# LEDSEQUENCER.net
KiCad netlist of a schematic drawn in Altium Designer
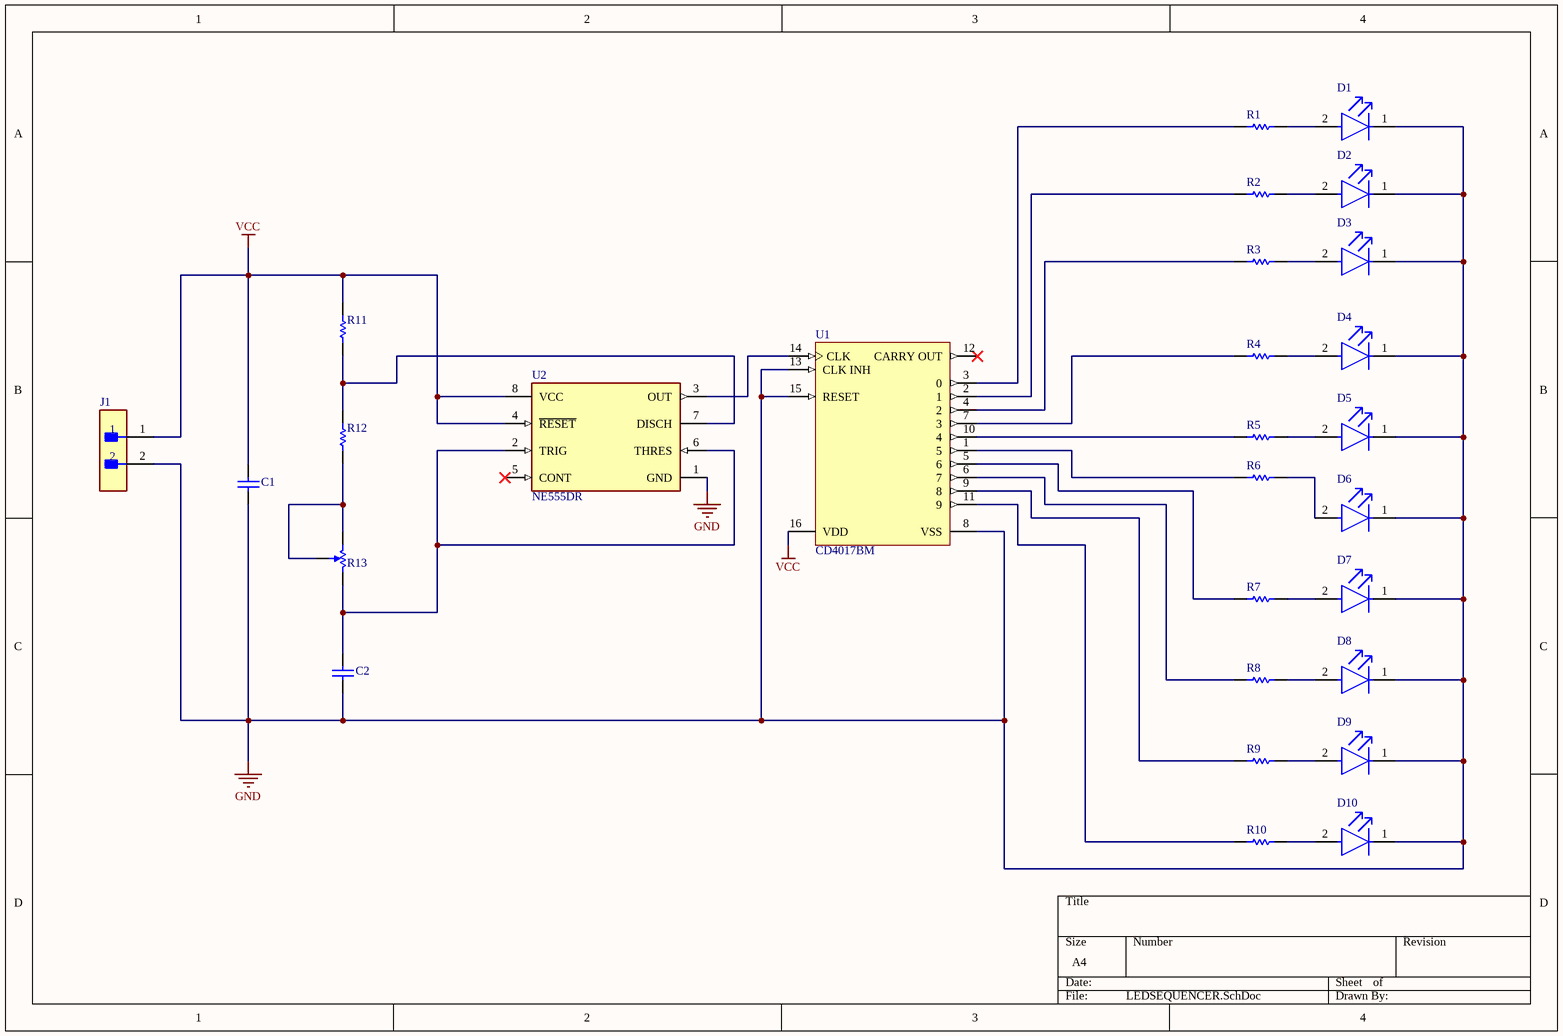
[diagram p0: LEDSEQUENCER.SchDoc]

(export (version "E")
  (design (tool "Eeschema 10.0.6"))
  (components
    (comp (ref "C1")
      (value "1uf")
      (footprint "CAPC2013X135X45LL10T25")
      (fields (field (name "MANUFACTURER") "Murata") (field (name "PART NUMBER") "GRM21BR71H105KA12L"))
      (libsource (lib "Altium Content Vault") (part "CAP"))
    )
    (comp (ref "C2")
      (value "1uf")
      (footprint "CAPC2013X135X45LL10T25")
      (fields (field (name "MANUFACTURER") "Murata") (field (name "PART NUMBER") "GRM21BR71H105KA12L"))
      (libsource (lib "Altium Content Vault") (part "CAP"))
    )
    (comp (ref "D1")
      (value "HLMP-1301")
      (footprint "FP-HLMP-1301-MFG")
      (description "LED RED DIFFUSED T-1 T/H")
      (fields
        (field (name "OCTOPART") "https://octopart.com/hlmp-1301-broadcom-71130345")
        (field (name "MANUFACTURER") "Broadcom")
      )
      (libsource (lib "Altium Content Vault") (part "8706943c75ba83719d021d2fdc84c58"))
    )
    (comp (ref "D2")
      (value "HLMP-1301")
      (footprint "FP-HLMP-1301-MFG")
      (description "LED RED DIFFUSED T-1 T/H")
      (fields
        (field (name "OCTOPART") "https://octopart.com/hlmp-1301-broadcom-71130345")
        (field (name "MANUFACTURER") "Broadcom")
      )
      (libsource (lib "Altium Content Vault") (part "8706943c75ba83719d021d2fdc84c58"))
    )
    (comp (ref "D3")
      (value "HLMP-1301")
      (footprint "FP-HLMP-1301-MFG")
      (description "LED RED DIFFUSED T-1 T/H")
      (fields
        (field (name "OCTOPART") "https://octopart.com/hlmp-1301-broadcom-71130345")
        (field (name "MANUFACTURER") "Broadcom")
      )
      (libsource (lib "Altium Content Vault") (part "8706943c75ba83719d021d2fdc84c58"))
    )
    (comp (ref "D4")
      (value "HLMP-1301")
      (footprint "FP-HLMP-1301-MFG")
      (description "LED RED DIFFUSED T-1 T/H")
      (fields
        (field (name "OCTOPART") "https://octopart.com/hlmp-1301-broadcom-71130345")
        (field (name "MANUFACTURER") "Broadcom")
      )
      (libsource (lib "Altium Content Vault") (part "8706943c75ba83719d021d2fdc84c58"))
    )
    (comp (ref "D5")
      (value "HLMP-1301")
      (footprint "FP-HLMP-1301-MFG")
      (description "LED RED DIFFUSED T-1 T/H")
      (fields
        (field (name "OCTOPART") "https://octopart.com/hlmp-1301-broadcom-71130345")
        (field (name "MANUFACTURER") "Broadcom")
      )
      (libsource (lib "Altium Content Vault") (part "8706943c75ba83719d021d2fdc84c58"))
    )
    (comp (ref "D6")
      (value "HLMP-1301")
      (footprint "FP-HLMP-1301-MFG")
      (description "LED RED DIFFUSED T-1 T/H")
      (fields
        (field (name "OCTOPART") "https://octopart.com/hlmp-1301-broadcom-71130345")
        (field (name "MANUFACTURER") "Broadcom")
      )
      (libsource (lib "Altium Content Vault") (part "8706943c75ba83719d021d2fdc84c58"))
    )
    (comp (ref "D7")
      (value "HLMP-1301")
      (footprint "FP-HLMP-1301-MFG")
      (description "LED RED DIFFUSED T-1 T/H")
      (fields
        (field (name "OCTOPART") "https://octopart.com/hlmp-1301-broadcom-71130345")
        (field (name "MANUFACTURER") "Broadcom")
      )
      (libsource (lib "Altium Content Vault") (part "8706943c75ba83719d021d2fdc84c58"))
    )
    (comp (ref "D8")
      (value "HLMP-1301")
      (footprint "FP-HLMP-1301-MFG")
      (description "LED RED DIFFUSED T-1 T/H")
      (fields
        (field (name "OCTOPART") "https://octopart.com/hlmp-1301-broadcom-71130345")
        (field (name "MANUFACTURER") "Broadcom")
      )
      (libsource (lib "Altium Content Vault") (part "8706943c75ba83719d021d2fdc84c58"))
    )
    (comp (ref "D9")
      (value "HLMP-1301")
      (footprint "FP-HLMP-1301-MFG")
      (description "LED RED DIFFUSED T-1 T/H")
      (fields
        (field (name "OCTOPART") "https://octopart.com/hlmp-1301-broadcom-71130345")
        (field (name "MANUFACTURER") "Broadcom")
      )
      (libsource (lib "Altium Content Vault") (part "8706943c75ba83719d021d2fdc84c58"))
    )
    (comp (ref "D10")
      (value "HLMP-1301")
      (footprint "FP-HLMP-1301-MFG")
      (description "LED RED DIFFUSED T-1 T/H")
      (fields
        (field (name "OCTOPART") "https://octopart.com/hlmp-1301-broadcom-71130345")
        (field (name "MANUFACTURER") "Broadcom")
      )
      (libsource (lib "Altium Content Vault") (part "8706943c75ba83719d021d2fdc84c58"))
    )
    (comp (ref "J1")
      (value "M20-9990246")
      (footprint "FP-M20-9990246-MFG")
      (description "CONN HEADER VERT 2POS 2.54MM")
      (fields
        (field (name "OCTOPART") "https://octopart.com/m20-9990246-harwin-2590635")
        (field (name "MANUFACTURER") "Harwin")
      )
      (libsource (lib "Altium Content Vault") (part "3bc925449376181038e59eaffc5286c"))
    )
    (comp (ref "R1")
      (value "RC0805FR-071KL")
      (footprint "RESC2013X60X35ML10T20")
      (description "Chip Resistor, 1 KOhm, +/- 1%, 125 mW, -55 to 155 degC, 0805 (2012 Metric), RoHS, Tape and Reel")
      (fields (field (name "TOLERANCE") "1%") (field (name "MANUFACTURER") "Yageo"))
      (libsource (lib "Altium Content Vault") (part "RES-2"))
    )
    (comp (ref "R2")
      (value "RC0805FR-071KL")
      (footprint "RESC2013X60X35ML10T20")
      (description "Chip Resistor, 1 KOhm, +/- 1%, 125 mW, -55 to 155 degC, 0805 (2012 Metric), RoHS, Tape and Reel")
      (fields (field (name "TOLERANCE") "1%") (field (name "MANUFACTURER") "Yageo"))
      (libsource (lib "Altium Content Vault") (part "RES-2"))
    )
    (comp (ref "R3")
      (value "RC0805FR-071KL")
      (footprint "RESC2013X60X35ML10T20")
      (description "Chip Resistor, 1 KOhm, +/- 1%, 125 mW, -55 to 155 degC, 0805 (2012 Metric), RoHS, Tape and Reel")
      (fields (field (name "TOLERANCE") "1%") (field (name "MANUFACTURER") "Yageo"))
      (libsource (lib "Altium Content Vault") (part "RES-2"))
    )
    (comp (ref "R4")
      (value "RC0805FR-071KL")
      (footprint "RESC2013X60X35ML10T20")
      (description "Chip Resistor, 1 KOhm, +/- 1%, 125 mW, -55 to 155 degC, 0805 (2012 Metric), RoHS, Tape and Reel")
      (fields (field (name "TOLERANCE") "1%") (field (name "MANUFACTURER") "Yageo"))
      (libsource (lib "Altium Content Vault") (part "RES-2"))
    )
    (comp (ref "R5")
      (value "RC0805FR-071KL")
      (footprint "RESC2013X60X35ML10T20")
      (description "Chip Resistor, 1 KOhm, +/- 1%, 125 mW, -55 to 155 degC, 0805 (2012 Metric), RoHS, Tape and Reel")
      (fields (field (name "TOLERANCE") "1%") (field (name "MANUFACTURER") "Yageo"))
      (libsource (lib "Altium Content Vault") (part "RES-2"))
    )
    (comp (ref "R6")
      (value "RC0805FR-071KL")
      (footprint "RESC2013X60X35ML10T20")
      (description "Chip Resistor, 1 KOhm, +/- 1%, 125 mW, -55 to 155 degC, 0805 (2012 Metric), RoHS, Tape and Reel")
      (fields (field (name "TOLERANCE") "1%") (field (name "MANUFACTURER") "Yageo"))
      (libsource (lib "Altium Content Vault") (part "RES-2"))
    )
    (comp (ref "R7")
      (value "RC0805FR-071KL")
      (footprint "RESC2013X60X35ML10T20")
      (description "Chip Resistor, 1 KOhm, +/- 1%, 125 mW, -55 to 155 degC, 0805 (2012 Metric), RoHS, Tape and Reel")
      (fields (field (name "TOLERANCE") "1%") (field (name "MANUFACTURER") "Yageo"))
      (libsource (lib "Altium Content Vault") (part "RES-2"))
    )
    (comp (ref "R8")
      (value "RC0805FR-071KL")
      (footprint "RESC2013X60X35ML10T20")
      (description "Chip Resistor, 1 KOhm, +/- 1%, 125 mW, -55 to 155 degC, 0805 (2012 Metric), RoHS, Tape and Reel")
      (fields (field (name "TOLERANCE") "1%") (field (name "MANUFACTURER") "Yageo"))
      (libsource (lib "Altium Content Vault") (part "RES-2"))
    )
    (comp (ref "R9")
      (value "RC0805FR-071KL")
      (footprint "RESC2013X60X35ML10T20")
      (description "Chip Resistor, 1 KOhm, +/- 1%, 125 mW, -55 to 155 degC, 0805 (2012 Metric), RoHS, Tape and Reel")
      (fields (field (name "TOLERANCE") "1%") (field (name "MANUFACTURER") "Yageo"))
      (libsource (lib "Altium Content Vault") (part "RES-2"))
    )
    (comp (ref "R10")
      (value "RC0805FR-071KL")
      (footprint "RESC2013X60X35ML10T20")
      (description "Chip Resistor, 1 KOhm, +/- 1%, 125 mW, -55 to 155 degC, 0805 (2012 Metric), RoHS, Tape and Reel")
      (fields (field (name "TOLERANCE") "1%") (field (name "MANUFACTURER") "Yageo"))
      (libsource (lib "Altium Content Vault") (part "RES-2"))
    )
    (comp (ref "R11")
      (value "2k2")
      (footprint "RESC2013X60X35ML10T20")
      (description "Chip Resistor, 1 KOhm, +/- 1%, 125 mW, -55 to 155 degC, 0805 (2012 Metric), RoHS, Tape and Reel")
      (fields (field (name "TOLERANCE") "1%") (field (name "MANUFACTURER") "Yageo"))
      (libsource (lib "Altium Content Vault") (part "RES-2"))
    )
    (comp (ref "R12")
      (value "10k")
      (footprint "RESC2013X60X35ML10T20")
      (description "Chip Resistor, 1 KOhm, +/- 1%, 125 mW, -55 to 155 degC, 0805 (2012 Metric), RoHS, Tape and Reel")
      (fields (field (name "TOLERANCE") "1%") (field (name "MANUFACTURER") "Yageo"))
      (libsource (lib "Altium Content Vault") (part "RES-2"))
    )
    (comp (ref "R13")
      (value "50k")
      (footprint "BOUR-3386P")
      (fields (field (name "TOLERANCE") "10%") (field (name "MANUFACTURER") "Bourns"))
      (libsource (lib "Altium Content Vault") (part "RES-ADJ-3_A"))
    )
    (comp (ref "U1")
      (value "CD4017BM")
      (footprint "D0016A_N")
      (description "CMOS Decade Counter with 10 Decoded Outputs, D0016A, TUBE")
      (fields
        (field (name "GENERIC PART NUMBER") "CD4017B")
        (field (name "MANUFACTURER") "Texas Instruments")
      )
      (libsource (lib "Altium Content Vault") (part "TI-CD4017B-16"))
    )
    (comp (ref "U2")
      (value "NE555DR")
      (footprint "FP-D0008A-IPC_A")
      (description "IC OSC SGL TIMER 100KHZ 8-SOIC")
      (libsource (lib "Altium Content Vault") (part "a29bba90211dec1890110b94dad7d53"))
    )
  )
  (nets
    (net (code "1") (name "GND") (class "Default")
      (node (ref "C1") (pin "1") (pinfunction "1_1") (pintype "passive"))
      (node (ref "C2") (pin "1") (pinfunction "1_1") (pintype "passive"))
      (node (ref "D1") (pin "1") (pinfunction "C_1") (pintype "passive"))
      (node (ref "D10") (pin "1") (pinfunction "C_1") (pintype "passive"))
      (node (ref "D2") (pin "1") (pinfunction "C_1") (pintype "passive"))
      (node (ref "D3") (pin "1") (pinfunction "C_1") (pintype "passive"))
      (node (ref "D4") (pin "1") (pinfunction "C_1") (pintype "passive"))
      (node (ref "D5") (pin "1") (pinfunction "C_1") (pintype "passive"))
      (node (ref "D6") (pin "1") (pinfunction "C_1") (pintype "passive"))
      (node (ref "D7") (pin "1") (pinfunction "C_1") (pintype "passive"))
      (node (ref "D8") (pin "1") (pinfunction "C_1") (pintype "passive"))
      (node (ref "D9") (pin "1") (pinfunction "C_1") (pintype "passive"))
      (node (ref "J1") (pin "2") (pinfunction "2_2") (pintype "passive"))
      (node (ref "U1") (pin "13") (pinfunction "CLK_INH_13") (pintype "input"))
      (node (ref "U1") (pin "15") (pinfunction "RESET_15") (pintype "input"))
      (node (ref "U1") (pin "8") (pinfunction "VSS_8") (pintype "power_in"))
      (node (ref "U2") (pin "1") (pinfunction "GND_1") (pintype "power_in"))
    )
    (net (code "2") (name "Net-(D1-A)") (class "Default")
      (node (ref "D1") (pin "2") (pinfunction "A_2") (pintype "passive"))
      (node (ref "R1") (pin "2") (pinfunction "2_2") (pintype "passive"))
    )
    (net (code "3") (name "Net-(D2-A)") (class "Default")
      (node (ref "D2") (pin "2") (pinfunction "A_2") (pintype "passive"))
      (node (ref "R2") (pin "2") (pinfunction "2_2") (pintype "passive"))
    )
    (net (code "4") (name "Net-(D3-A)") (class "Default")
      (node (ref "D3") (pin "2") (pinfunction "A_2") (pintype "passive"))
      (node (ref "R3") (pin "2") (pinfunction "2_2") (pintype "passive"))
    )
    (net (code "5") (name "Net-(D4-A)") (class "Default")
      (node (ref "D4") (pin "2") (pinfunction "A_2") (pintype "passive"))
      (node (ref "R4") (pin "2") (pinfunction "2_2") (pintype "passive"))
    )
    (net (code "6") (name "Net-(D5-A)") (class "Default")
      (node (ref "D5") (pin "2") (pinfunction "A_2") (pintype "passive"))
      (node (ref "R5") (pin "2") (pinfunction "2_2") (pintype "passive"))
    )
    (net (code "7") (name "Net-(D6-A)") (class "Default")
      (node (ref "D6") (pin "2") (pinfunction "A_2") (pintype "passive"))
      (node (ref "R6") (pin "2") (pinfunction "2_2") (pintype "passive"))
    )
    (net (code "8") (name "Net-(D7-A)") (class "Default")
      (node (ref "D7") (pin "2") (pinfunction "A_2") (pintype "passive"))
      (node (ref "R7") (pin "2") (pinfunction "2_2") (pintype "passive"))
    )
    (net (code "9") (name "Net-(D8-A)") (class "Default")
      (node (ref "D8") (pin "2") (pinfunction "A_2") (pintype "passive"))
      (node (ref "R8") (pin "2") (pinfunction "2_2") (pintype "passive"))
    )
    (net (code "10") (name "Net-(D9-A)") (class "Default")
      (node (ref "D9") (pin "2") (pinfunction "A_2") (pintype "passive"))
      (node (ref "R9") (pin "2") (pinfunction "2_2") (pintype "passive"))
    )
    (net (code "11") (name "Net-(D10-A)") (class "Default")
      (node (ref "D10") (pin "2") (pinfunction "A_2") (pintype "passive"))
      (node (ref "R10") (pin "2") (pinfunction "2_2") (pintype "passive"))
    )
    (net (code "12") (name "Net-(R12-Pad1)") (class "Default")
      (node (ref "R12") (pin "1") (pinfunction "1_1") (pintype "passive"))
      (node (ref "R13") (pin "2") (pinfunction "2_2") (pintype "passive"))
      (node (ref "R13") (pin "3") (pinfunction "3_3") (pintype "passive"))
    )
    (net (code "13") (name "Net-(U1-0)") (class "Default")
      (node (ref "R1") (pin "1") (pinfunction "1_1") (pintype "passive"))
      (node (ref "U1") (pin "3") (pinfunction "0_3") (pintype "output"))
    )
    (net (code "14") (name "Net-(U1-1)") (class "Default")
      (node (ref "R2") (pin "1") (pinfunction "1_1") (pintype "passive"))
      (node (ref "U1") (pin "2") (pinfunction "1_2") (pintype "output"))
    )
    (net (code "15") (name "Net-(U1-2)") (class "Default")
      (node (ref "R3") (pin "1") (pinfunction "1_1") (pintype "passive"))
      (node (ref "U1") (pin "4") (pinfunction "2_4") (pintype "output"))
    )
    (net (code "16") (name "Net-(U1-3)") (class "Default")
      (node (ref "R4") (pin "1") (pinfunction "1_1") (pintype "passive"))
      (node (ref "U1") (pin "7") (pinfunction "3_7") (pintype "output"))
    )
    (net (code "17") (name "Net-(U1-4)") (class "Default")
      (node (ref "R5") (pin "1") (pinfunction "1_1") (pintype "passive"))
      (node (ref "U1") (pin "10") (pinfunction "4_10") (pintype "output"))
    )
    (net (code "18") (name "Net-(U1-5)") (class "Default")
      (node (ref "R6") (pin "1") (pinfunction "1_1") (pintype "passive"))
      (node (ref "U1") (pin "1") (pinfunction "5_1") (pintype "output"))
    )
    (net (code "19") (name "Net-(U1-6)") (class "Default")
      (node (ref "R7") (pin "1") (pinfunction "1_1") (pintype "passive"))
      (node (ref "U1") (pin "5") (pinfunction "6_5") (pintype "output"))
    )
    (net (code "20") (name "Net-(U1-7)") (class "Default")
      (node (ref "R8") (pin "1") (pinfunction "1_1") (pintype "passive"))
      (node (ref "U1") (pin "6") (pinfunction "7_6") (pintype "output"))
    )
    (net (code "21") (name "Net-(U1-8)") (class "Default")
      (node (ref "R9") (pin "1") (pinfunction "1_1") (pintype "passive"))
      (node (ref "U1") (pin "9") (pinfunction "8_9") (pintype "output"))
    )
    (net (code "22") (name "Net-(U1-9)") (class "Default")
      (node (ref "R10") (pin "1") (pinfunction "1_1") (pintype "passive"))
      (node (ref "U1") (pin "11") (pinfunction "9_11") (pintype "output"))
    )
    (net (code "23") (name "Net-(U1-CLK)") (class "Default")
      (node (ref "U1") (pin "14") (pinfunction "CLK_14") (pintype "input"))
      (node (ref "U2") (pin "3") (pinfunction "OUT_3") (pintype "output"))
    )
    (net (code "24") (name "Net-(U2-DISCH)") (class "Default")
      (node (ref "R11") (pin "1") (pinfunction "1_1") (pintype "passive"))
      (node (ref "R12") (pin "2") (pinfunction "2_2") (pintype "passive"))
      (node (ref "U2") (pin "7") (pinfunction "DISCH_7") (pintype "open_collector"))
    )
    (net (code "25") (name "Net-(U2-THRES)") (class "Default")
      (node (ref "C2") (pin "2") (pinfunction "2_2") (pintype "passive"))
      (node (ref "R13") (pin "1") (pinfunction "1_1") (pintype "passive"))
      (node (ref "U2") (pin "2") (pinfunction "TRIG_2") (pintype "input"))
      (node (ref "U2") (pin "6") (pinfunction "THRES_6") (pintype "input"))
    )
    (net (code "26") (name "VCC") (class "Default")
      (node (ref "C1") (pin "2") (pinfunction "2_2") (pintype "passive"))
      (node (ref "J1") (pin "1") (pinfunction "1_1") (pintype "passive"))
      (node (ref "R11") (pin "2") (pinfunction "2_2") (pintype "passive"))
      (node (ref "U1") (pin "16") (pinfunction "VDD_16") (pintype "power_in"))
      (node (ref "U2") (pin "4") (pinfunction "~{RESET}_4") (pintype "input"))
      (node (ref "U2") (pin "8") (pinfunction "VCC_8") (pintype "power_in"))
    )
    (net (code "27") (name "unconnected-(U1-CARRY_OUT-Pad12)") (class "Default")
      (node (ref "U1") (pin "12") (pinfunction "CARRY_OUT_12") (pintype "output+no_connect"))
    )
    (net (code "28") (name "unconnected-(U2-CONT-Pad5)") (class "Default")
      (node (ref "U2") (pin "5") (pinfunction "CONT_5") (pintype "input+no_connect"))
    )
  )
)
